# EGT003.net
KiCad netlist of a schematic drawn in Altium Designer
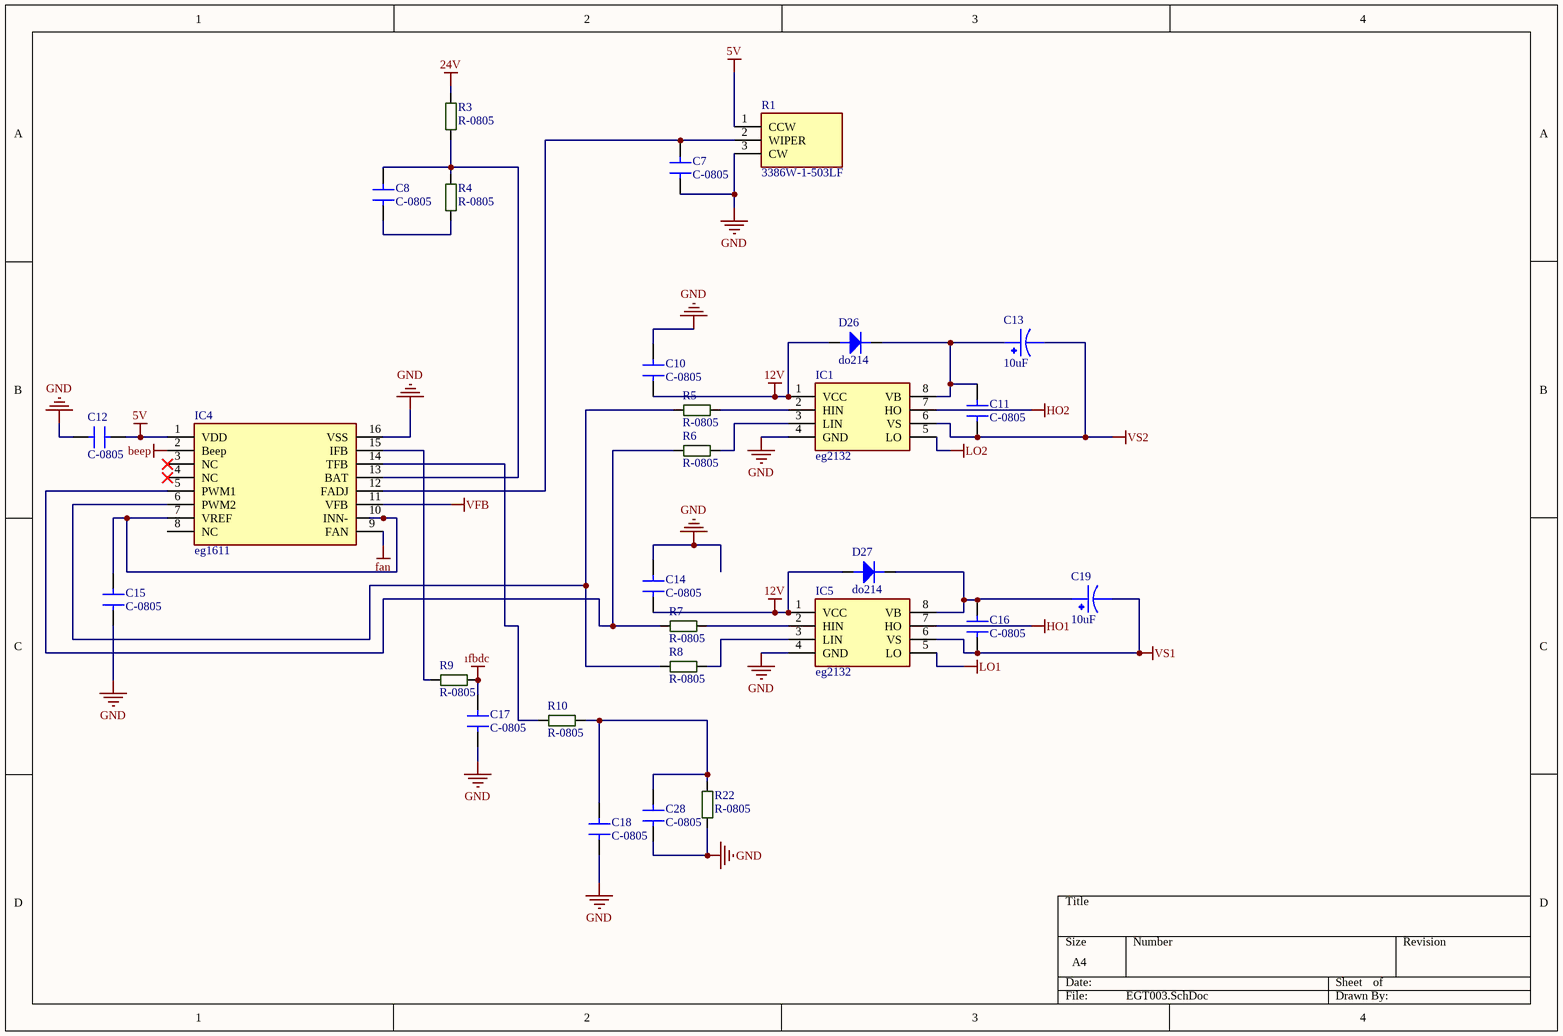
[diagram p0: EGT003.SchDoc]

(export (version "E")
  (design (tool "Eeschema 10.0.6"))
  (components
    (comp (ref "C7") (value "C-0805") (footprint "C-0805W") (libsource (lib "Schlib1") (part "C-0805")))
    (comp (ref "C8") (value "C-0805") (footprint "C-0805W") (libsource (lib "Schlib1") (part "C-0805")))
    (comp (ref "C10") (value "C-0805") (footprint "C-0805W") (libsource (lib "Schlib1") (part "C-0805")))
    (comp (ref "C11") (value "C-0805") (footprint "C-0805W") (libsource (lib "Schlib1") (part "C-0805")))
    (comp (ref "C12") (value "C-0805") (footprint "C-0805W") (libsource (lib "Schlib1") (part "C-0805")))
    (comp (ref "C13")
      (value "10uF")
      (footprint "CapSmdElc")
      (libsource (lib "PROJE") (part "100 uF Electr Cap"))
    )
    (comp (ref "C14") (value "C-0805") (footprint "C-0805W") (libsource (lib "Schlib1") (part "C-0805")))
    (comp (ref "C15") (value "C-0805") (footprint "C-0805W") (libsource (lib "Schlib1") (part "C-0805")))
    (comp (ref "C16") (value "C-0805") (footprint "C-0805W") (libsource (lib "Schlib1") (part "C-0805")))
    (comp (ref "C17") (value "C-0805") (footprint "C-0805W") (libsource (lib "Schlib1") (part "C-0805")))
    (comp (ref "C18") (value "C-0805") (footprint "C-0805W") (libsource (lib "Schlib1") (part "C-0805")))
    (comp (ref "C19")
      (value "10uF")
      (footprint "CapSmdElc")
      (libsource (lib "PROJE") (part "100 uF Electr Cap"))
    )
    (comp (ref "C28") (value "C-0805") (footprint "C-0805W") (libsource (lib "Schlib1") (part "C-0805")))
    (comp (ref "D26")
      (value "do214")
      (footprint "DO-214AC")
      (description "DIODE FAST SWITCHING Single 150mA 75V SMT SOD323")
      (libsource (lib "Schlib1") (part "do214"))
    )
    (comp (ref "D27")
      (value "do214")
      (footprint "DO-214AC")
      (description "DIODE FAST SWITCHING Single 150mA 75V SMT SOD323")
      (libsource (lib "Schlib1") (part "do214"))
    )
    (comp (ref "IC1")
      (value "eg2132")
      (footprint "SOIC127P600X175-8N")
      (description "Integrated Circuit")
      (fields
        (field (name "MANUFACTURER_PART_NUMBER") "LM393ADR")
        (field (name "MOUSER PART NUMBER") "595-LM393ADR")
      )
      (libsource (lib "Schlib1") (part "eg2132"))
    )
    (comp (ref "IC4")
      (value "eg1611")
      (footprint "SamacSys:SOIC127P600X175-16N")
      (description "Integrated Circuit")
      (fields
        (field (name "MANUFACTURER_PART_NUMBER") "HCF4538M013TR")
        (field (name "MOUSER PART NUMBER") "511-4538BM-TR")
      )
      (libsource (lib "Schlib1") (part "eg1611"))
    )
    (comp (ref "IC5")
      (value "eg2132")
      (footprint "SOIC127P600X175-8N")
      (description "Integrated Circuit")
      (fields
        (field (name "MANUFACTURER_PART_NUMBER") "LM393ADR")
        (field (name "MOUSER PART NUMBER") "595-LM393ADR")
      )
      (libsource (lib "Schlib1") (part "eg2132"))
    )
    (comp (ref "R1")
      (value "3386W-1-503LF")
      (footprint "SamacSys:3386W")
      (description "Resistor")
      (fields (field (name "MOUSER PART NUMBER") "652-3386W-1-503LF"))
      (libsource (lib "*") (part "3386W-1-503LF"))
    )
    (comp (ref "R3") (value "R-0805") (footprint "R-0805W") (libsource (lib "Schlib1") (part "R-0805")))
    (comp (ref "R4") (value "R-0805") (footprint "R-0805W") (libsource (lib "Schlib1") (part "R-0805")))
    (comp (ref "R5") (value "R-0805") (footprint "R-0805W") (libsource (lib "Schlib1") (part "R-0805")))
    (comp (ref "R6") (value "R-0805") (footprint "R-0805W") (libsource (lib "Schlib1") (part "R-0805")))
    (comp (ref "R7") (value "R-0805") (footprint "R-0805W") (libsource (lib "Schlib1") (part "R-0805")))
    (comp (ref "R8") (value "R-0805") (footprint "R-0805W") (libsource (lib "Schlib1") (part "R-0805")))
    (comp (ref "R9") (value "R-0805") (footprint "R-0805W") (libsource (lib "Schlib1") (part "R-0805")))
    (comp (ref "R10") (value "R-0805") (footprint "R-0805W") (libsource (lib "Schlib1") (part "R-0805")))
    (comp (ref "R22") (value "R-0805") (footprint "R-0805W") (libsource (lib "Schlib1") (part "R-0805")))
  )
  (nets
    (net (code "1") (name "5V") (class "Default")
      (node (ref "C12") (pin "2") (pinfunction "2_2") (pintype "passive"))
      (node (ref "IC4") (pin "1") (pinfunction "VDD_1") (pintype "passive"))
      (node (ref "R1") (pin "1") (pinfunction "CCW_1") (pintype "passive"))
    )
    (net (code "2") (name "12V") (class "Default")
      (node (ref "C10") (pin "1") (pinfunction "1_1") (pintype "passive"))
      (node (ref "C14") (pin "1") (pinfunction "1_1") (pintype "passive"))
      (node (ref "D26") (pin "a") (pinfunction "a_a") (pintype "passive"))
      (node (ref "D27") (pin "a") (pinfunction "a_a") (pintype "passive"))
      (node (ref "IC1") (pin "1") (pinfunction "VCC_1") (pintype "passive"))
      (node (ref "IC5") (pin "1") (pinfunction "VCC_1") (pintype "passive"))
    )
    (net (code "3") (name "24V") (class "Default")
      (node (ref "R3") (pin "2") (pinfunction "2_2") (pintype "passive"))
    )
    (net (code "4") (name "GND") (class "Default")
      (node (ref "C10") (pin "2") (pinfunction "2_2") (pintype "passive"))
      (node (ref "C12") (pin "1") (pinfunction "1_1") (pintype "passive"))
      (node (ref "C14") (pin "2") (pinfunction "2_2") (pintype "passive"))
      (node (ref "C15") (pin "1") (pinfunction "1_1") (pintype "passive"))
      (node (ref "C17") (pin "1") (pinfunction "1_1") (pintype "passive"))
      (node (ref "C18") (pin "1") (pinfunction "1_1") (pintype "passive"))
      (node (ref "C28") (pin "1") (pinfunction "1_1") (pintype "passive"))
      (node (ref "C7") (pin "1") (pinfunction "1_1") (pintype "passive"))
      (node (ref "IC1") (pin "4") (pinfunction "GND_4") (pintype "passive"))
      (node (ref "IC4") (pin "16") (pinfunction "VSS_16") (pintype "passive"))
      (node (ref "IC5") (pin "4") (pinfunction "GND_4") (pintype "passive"))
      (node (ref "R1") (pin "3") (pinfunction "CW_3") (pintype "passive"))
      (node (ref "R22") (pin "1") (pinfunction "1_1") (pintype "passive"))
    )
    (net (code "5") (name "HO1") (class "Default")
      (node (ref "IC5") (pin "7") (pinfunction "HO_7") (pintype "passive"))
    )
    (net (code "6") (name "HO2") (class "Default")
      (node (ref "IC1") (pin "7") (pinfunction "HO_7") (pintype "passive"))
    )
    (net (code "7") (name "LO1") (class "Default")
      (node (ref "IC5") (pin "5") (pinfunction "LO_5") (pintype "passive"))
    )
    (net (code "8") (name "LO2") (class "Default")
      (node (ref "IC1") (pin "5") (pinfunction "LO_5") (pintype "passive"))
    )
    (net (code "9") (name "Net-(C8-Pad1)") (class "Default")
      (node (ref "C8") (pin "1") (pinfunction "1_1") (pintype "passive"))
      (node (ref "R4") (pin "1") (pinfunction "1_1") (pintype "passive"))
    )
    (net (code "10") (name "Net-(C18-Pad2)") (class "Default")
      (node (ref "C18") (pin "2") (pinfunction "2_2") (pintype "passive"))
      (node (ref "C28") (pin "2") (pinfunction "2_2") (pintype "passive"))
      (node (ref "R10") (pin "1") (pinfunction "1_1") (pintype "passive"))
      (node (ref "R22") (pin "2") (pinfunction "2_2") (pintype "passive"))
    )
    (net (code "11") (name "Net-(IC1-HIN)") (class "Default")
      (node (ref "IC1") (pin "2") (pinfunction "HIN_2") (pintype "passive"))
      (node (ref "R5") (pin "1") (pinfunction "1_1") (pintype "passive"))
    )
    (net (code "12") (name "Net-(IC1-LIN)") (class "Default")
      (node (ref "IC1") (pin "3") (pinfunction "LIN_3") (pintype "passive"))
      (node (ref "R6") (pin "1") (pinfunction "1_1") (pintype "passive"))
    )
    (net (code "13") (name "Net-(IC1-VB)") (class "Default")
      (node (ref "C11") (pin "2") (pinfunction "2_2") (pintype "passive"))
      (node (ref "C13") (pin "1") (pinfunction "1_1") (pintype "passive"))
      (node (ref "D26") (pin "k") (pinfunction "k_k") (pintype "passive"))
      (node (ref "IC1") (pin "8") (pinfunction "VB_8") (pintype "passive"))
    )
    (net (code "14") (name "Net-(IC4-BAT)") (class "Default")
      (node (ref "C8") (pin "2") (pinfunction "2_2") (pintype "passive"))
      (node (ref "IC4") (pin "13") (pinfunction "BAT_13") (pintype "passive"))
      (node (ref "R3") (pin "1") (pinfunction "1_1") (pintype "passive"))
      (node (ref "R4") (pin "2") (pinfunction "2_2") (pintype "passive"))
    )
    (net (code "15") (name "Net-(IC4-FADJ)") (class "Default")
      (node (ref "C7") (pin "2") (pinfunction "2_2") (pintype "passive"))
      (node (ref "IC4") (pin "12") (pinfunction "FADJ_12") (pintype "passive"))
      (node (ref "R1") (pin "2") (pinfunction "WIPER_2") (pintype "passive"))
    )
    (net (code "16") (name "Net-(IC4-IFB)") (class "Default")
      (node (ref "IC4") (pin "15") (pinfunction "IFB_15") (pintype "passive"))
      (node (ref "R9") (pin "2") (pinfunction "2_2") (pintype "passive"))
    )
    (net (code "17") (name "Net-(IC4-INN-)") (class "Default")
      (node (ref "C15") (pin "2") (pinfunction "2_2") (pintype "passive"))
      (node (ref "IC4") (pin "10") (pinfunction "INN-_10") (pintype "passive"))
      (node (ref "IC4") (pin "7") (pinfunction "VREF_7") (pintype "passive"))
    )
    (net (code "18") (name "Net-(IC4-PWM1)") (class "Default")
      (node (ref "IC4") (pin "5") (pinfunction "PWM1_5") (pintype "passive"))
      (node (ref "R6") (pin "2") (pinfunction "2_2") (pintype "passive"))
      (node (ref "R7") (pin "2") (pinfunction "2_2") (pintype "passive"))
    )
    (net (code "19") (name "Net-(IC4-PWM2)") (class "Default")
      (node (ref "IC4") (pin "6") (pinfunction "PWM2_6") (pintype "passive"))
      (node (ref "R5") (pin "2") (pinfunction "2_2") (pintype "passive"))
      (node (ref "R8") (pin "2") (pinfunction "2_2") (pintype "passive"))
    )
    (net (code "20") (name "Net-(IC4-TFB)") (class "Default")
      (node (ref "IC4") (pin "14") (pinfunction "TFB_14") (pintype "passive"))
      (node (ref "R10") (pin "2") (pinfunction "2_2") (pintype "passive"))
    )
    (net (code "21") (name "Net-(IC5-HIN)") (class "Default")
      (node (ref "IC5") (pin "2") (pinfunction "HIN_2") (pintype "passive"))
      (node (ref "R7") (pin "1") (pinfunction "1_1") (pintype "passive"))
    )
    (net (code "22") (name "Net-(IC5-LIN)") (class "Default")
      (node (ref "IC5") (pin "3") (pinfunction "LIN_3") (pintype "passive"))
      (node (ref "R8") (pin "1") (pinfunction "1_1") (pintype "passive"))
    )
    (net (code "23") (name "Net-(IC5-VB)") (class "Default")
      (node (ref "C16") (pin "2") (pinfunction "2_2") (pintype "passive"))
      (node (ref "C19") (pin "1") (pinfunction "1_1") (pintype "passive"))
      (node (ref "D27") (pin "k") (pinfunction "k_k") (pintype "passive"))
      (node (ref "IC5") (pin "8") (pinfunction "VB_8") (pintype "passive"))
    )
    (net (code "24") (name "VFB") (class "Default")
      (node (ref "IC4") (pin "11") (pinfunction "VFB_11") (pintype "passive"))
    )
    (net (code "25") (name "VS1") (class "Default")
      (node (ref "C16") (pin "1") (pinfunction "1_1") (pintype "passive"))
      (node (ref "C19") (pin "2") (pinfunction "2_2") (pintype "passive"))
      (node (ref "IC5") (pin "6") (pinfunction "VS_6") (pintype "passive"))
    )
    (net (code "26") (name "VS2") (class "Default")
      (node (ref "C11") (pin "1") (pinfunction "1_1") (pintype "passive"))
      (node (ref "C13") (pin "2") (pinfunction "2_2") (pintype "passive"))
      (node (ref "IC1") (pin "6") (pinfunction "VS_6") (pintype "passive"))
    )
    (net (code "27") (name "beep") (class "Default")
      (node (ref "IC4") (pin "2") (pinfunction "Beep_2") (pintype "passive"))
    )
    (net (code "28") (name "fan") (class "Default")
      (node (ref "IC4") (pin "9") (pinfunction "FAN_9") (pintype "passive"))
    )
    (net (code "29") (name "unconnected-(IC4-NC-Pad3)") (class "Default")
      (node (ref "IC4") (pin "3") (pinfunction "NC_3") (pintype "passive+no_connect"))
    )
    (net (code "30") (name "unconnected-(IC4-NC-Pad4)") (class "Default")
      (node (ref "IC4") (pin "4") (pinfunction "NC_4") (pintype "passive+no_connect"))
    )
    (net (code "31") (name "unconnected-(IC4-NC-Pad8)") (class "Default")
      (node (ref "IC4") (pin "8") (pinfunction "NC_8") (pintype "passive"))
    )
    (net (code "32") (name "ıfbdc") (class "Default")
      (node (ref "C17") (pin "2") (pinfunction "2_2") (pintype "passive"))
      (node (ref "R9") (pin "1") (pinfunction "1_1") (pintype "passive"))
    )
  )
)
